# Power_24V_Rev1_1.net
KiCad netlist of a schematic drawn in Altium Designer
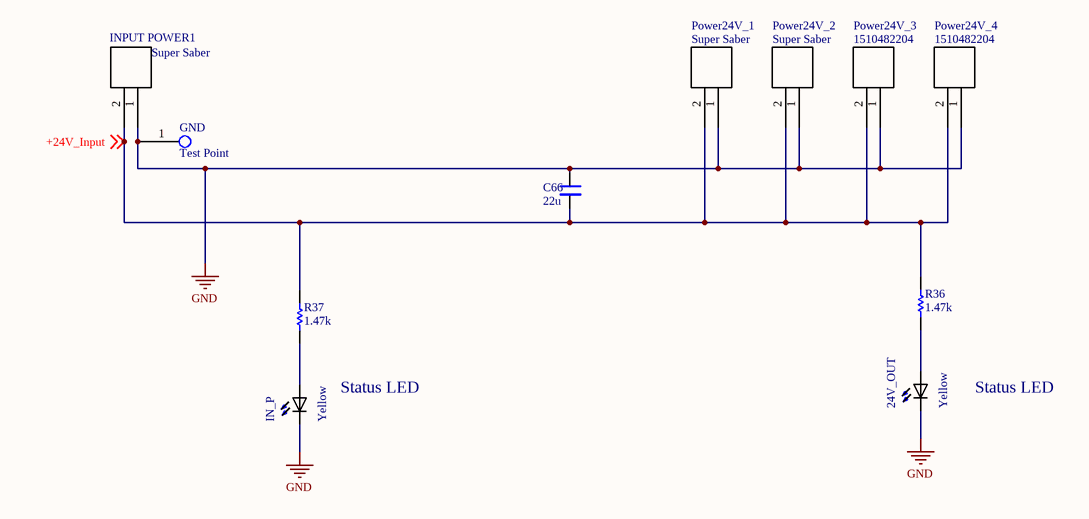
[diagram p0: Power_24V_Rev1.1.SchDoc]

(export (version "E")
  (design (tool "Eeschema 10.0.6"))
  (components
    (comp (ref "24V_OUT")
      (value "Yellow")
      (footprint "*DIOC200X125X110_LTST-C171KSKT(Primary)")
      (description "Yellow 2 x 1.25 x 0.8 mm 130Â° Water Clear 50 mcd 2 V LED SMT")
      (fields (field (name "MP") "LTST-C171KSKT") (field (name "DIGI-KEY_PART_NUMBER") "160-1428-1-ND"))
      (libsource (lib "LTST-C171KSKT") (part "LTST-C171KSKT"))
    )
    (comp (ref "C66")
      (value "22u")
      (footprint "*CAPC2012X88N")
      (description "100pF Â±5% 250V Ceramic Capacitor C0G, NP0 0805 _2012 Metric_")
      (fields (field (name "MF") "KEMET") (field (name "DIGI-KEY_PART_NUMBER") "399-15000-1-ND"))
      (libsource (lib "C0805C101JAGAC7800") (part "C0805C101JAGAC7800"))
    )
    (comp (ref "GND")
      (value "Test Point")
      (footprint "Test Point Through-hole")
      (libsource (lib "Test Points") (part "Test Point"))
    )
    (comp (ref "INPUT POWER1")
      (value "Super Saber")
      (footprint "1720420202")
      (libsource (lib "Connector Schematic Symbols") (part "Super Saber"))
    )
    (comp (ref "IN_P")
      (value "Yellow")
      (footprint "*DIOC200X125X110_LTST-C171KSKT(Primary)")
      (description "Yellow 2 x 1.25 x 0.8 mm 130Â° Water Clear 50 mcd 2 V LED SMT")
      (fields (field (name "MP") "LTST-C171KSKT") (field (name "DIGI-KEY_PART_NUMBER") "160-1428-1-ND"))
      (libsource (lib "LTST-C171KSKT") (part "LTST-C171KSKT"))
    )
    (comp (ref "Power24V_1")
      (value "Super Saber")
      (footprint "1720420202")
      (libsource (lib "Connector Schematic Symbols") (part "Super Saber"))
    )
    (comp (ref "Power24V_2")
      (value "Super Saber")
      (footprint "1720420202")
      (libsource (lib "Connector Schematic Symbols") (part "Super Saber"))
    )
    (comp (ref "Power24V_3")
      (value "1510482204")
      (footprint "1510482204")
      (description "Molex 6.5MM 2 pin connector, used for power connections. P/N 1510482204 and similar models.")
      (libsource (lib "Power Distribution") (part "1510482204"))
    )
    (comp (ref "Power24V_4")
      (value "1510482204")
      (footprint "1510482204")
      (description "Molex 6.5MM 2 pin connector, used for power connections. P/N 1510482204 and similar models.")
      (libsource (lib "Power Distribution") (part "1510482204"))
    )
    (comp (ref "R36")
      (value "1.47k")
      (footprint "RESC0805(2012)_M")
      (description "8M06 0.125W 1% 0805 (2012 Metric)  SMD")
      (fields (field (name "POWER") "0.125 W") (field (name "TOLERANCE") "1 %"))
      (libsource (lib "Altium Content Vault") (part "RES"))
    )
    (comp (ref "R37")
      (value "1.47k")
      (footprint "RESC0805(2012)_M")
      (description "8M06 0.125W 1% 0805 (2012 Metric)  SMD")
      (fields (field (name "POWER") "0.125 W") (field (name "TOLERANCE") "1 %"))
      (libsource (lib "Altium Content Vault") (part "RES"))
    )
  )
  (nets
    (net (code "1") (name "+24V_Input") (class "Default")
      (node (ref "C66") (pin "1") (pinfunction "1_1") (pintype "passive"))
      (node (ref "INPUT POWER1") (pin "2") (pintype "passive"))
      (node (ref "Power24V_1") (pin "2") (pintype "passive"))
      (node (ref "Power24V_2") (pin "2") (pintype "passive"))
      (node (ref "Power24V_3") (pin "2") (pintype "passive"))
      (node (ref "Power24V_4") (pin "2") (pintype "passive"))
      (node (ref "R36") (pin "2") (pinfunction "2_2") (pintype "passive"))
      (node (ref "R37") (pin "2") (pinfunction "2_2") (pintype "passive"))
    )
    (net (code "2") (name "GND") (class "Default")
      (node (ref "24V_OUT") (pin "NEG") (pinfunction "NEG_NEG") (pintype "passive"))
      (node (ref "C66") (pin "2") (pinfunction "2_2") (pintype "passive"))
      (node (ref "GND") (pin "1") (pinfunction "1_1") (pintype "passive"))
      (node (ref "INPUT POWER1") (pin "1") (pintype "passive"))
      (node (ref "IN_P") (pin "NEG") (pinfunction "NEG_NEG") (pintype "passive"))
      (node (ref "Power24V_1") (pin "1") (pintype "passive"))
      (node (ref "Power24V_2") (pin "1") (pintype "passive"))
      (node (ref "Power24V_3") (pin "1") (pintype "passive"))
      (node (ref "Power24V_4") (pin "1") (pintype "passive"))
    )
    (net (code "3") (name "Net-(24V_OUT-PadPOS)") (class "Default")
      (node (ref "24V_OUT") (pin "POS") (pinfunction "POS_POS") (pintype "passive"))
      (node (ref "R36") (pin "1") (pinfunction "1_1") (pintype "passive"))
    )
    (net (code "4") (name "Net-(IN_P-PadPOS)") (class "Default")
      (node (ref "IN_P") (pin "POS") (pinfunction "POS_POS") (pintype "passive"))
      (node (ref "R37") (pin "1") (pinfunction "1_1") (pintype "passive"))
    )
  )
)
